# thumper_v0001.net
KiCad netlist of a schematic drawn in EAGLE
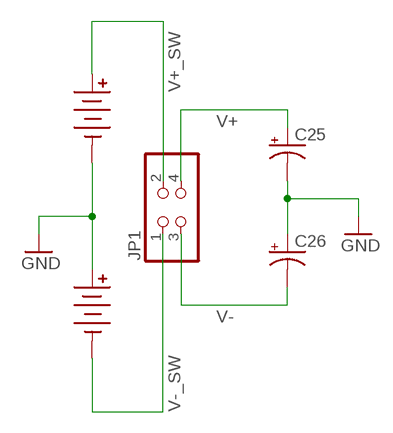
[diagram p0: schematic, sheet 1]
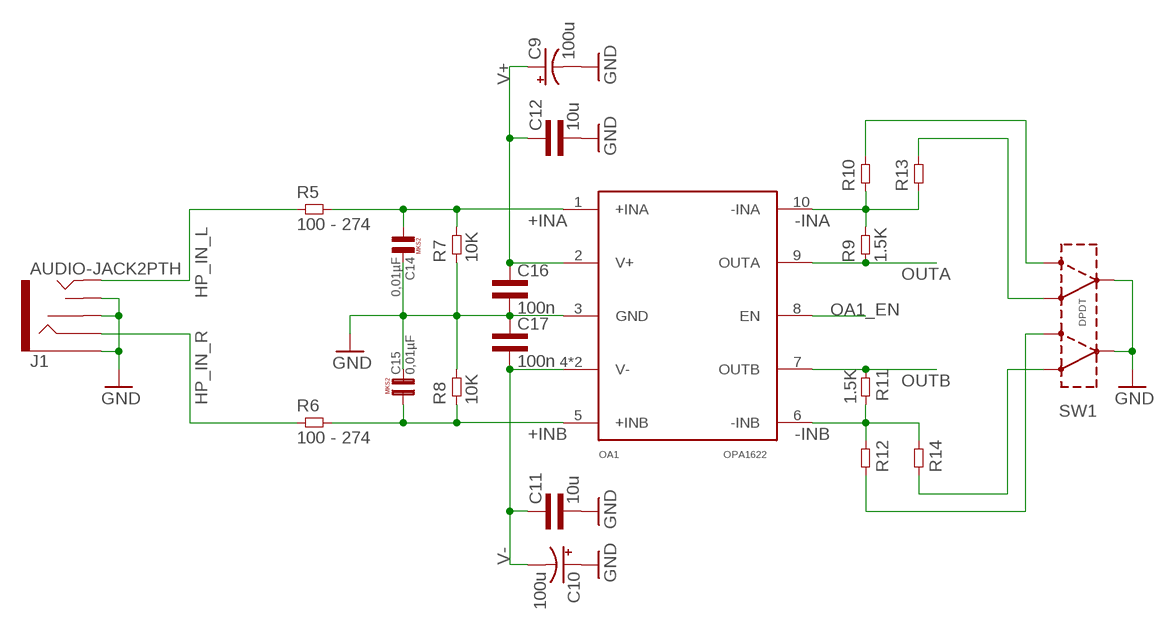
[diagram p1: schematic, sheet 2]
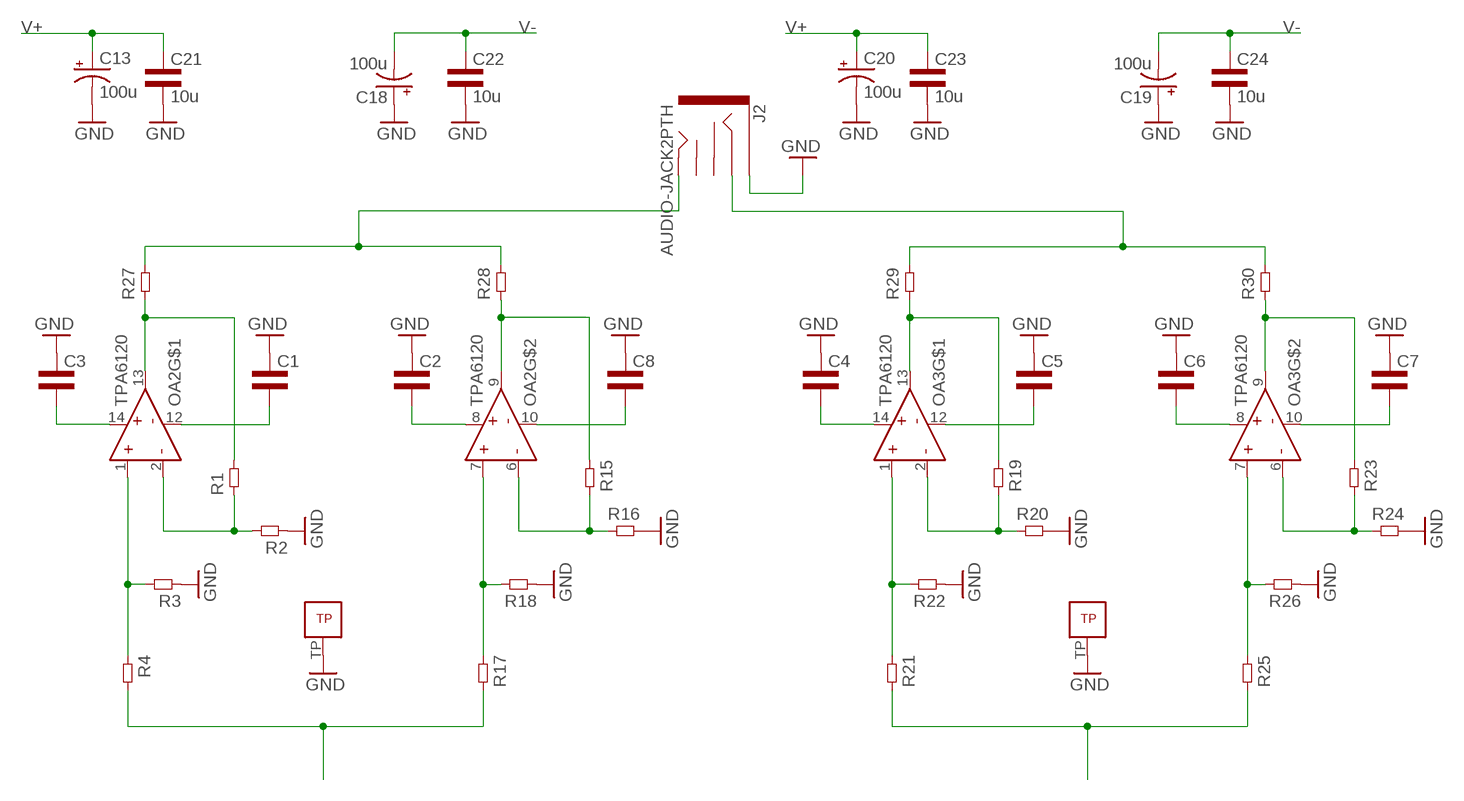
[diagram p2: schematic, sheet 3]

(export (version "E")
  (design (tool "Eeschema 10.0.6"))
  (components
    (comp (ref "C1")
      (value "CAP0603L3")
      (footprint "eagle-import:0603L3")
      (libsource (lib "eagle-import") (part "CAP0603L3"))
    )
    (comp (ref "C2")
      (value "CAP0603L3")
      (footprint "eagle-import:0603L3")
      (libsource (lib "eagle-import") (part "CAP0603L3"))
    )
    (comp (ref "C3")
      (value "CAP0603L3")
      (footprint "eagle-import:0603L3")
      (libsource (lib "eagle-import") (part "CAP0603L3"))
    )
    (comp (ref "C4")
      (value "CAP0603L3")
      (footprint "eagle-import:0603L3")
      (libsource (lib "eagle-import") (part "CAP0603L3"))
    )
    (comp (ref "C5")
      (value "CAP0603L3")
      (footprint "eagle-import:0603L3")
      (libsource (lib "eagle-import") (part "CAP0603L3"))
    )
    (comp (ref "C6")
      (value "CAP0603L3")
      (footprint "eagle-import:0603L3")
      (libsource (lib "eagle-import") (part "CAP0603L3"))
    )
    (comp (ref "C7")
      (value "CAP0603L3")
      (footprint "eagle-import:0603L3")
      (libsource (lib "eagle-import") (part "CAP0603L3"))
    )
    (comp (ref "C8")
      (value "CAP0603L3")
      (footprint "eagle-import:0603L3")
      (libsource (lib "eagle-import") (part "CAP0603L3"))
    )
    (comp (ref "C13")
      (value "100u")
      (footprint "eagle-import:CT7343")
      (libsource (lib "eagle-import") (part "CPOL-USCT7343"))
    )
    (comp (ref "C18")
      (value "100u")
      (footprint "eagle-import:CT7343")
      (libsource (lib "eagle-import") (part "CPOL-USCT7343"))
    )
    (comp (ref "C19")
      (value "100u")
      (footprint "eagle-import:CT7343")
      (libsource (lib "eagle-import") (part "CPOL-USCT7343"))
    )
    (comp (ref "C20")
      (value "100u")
      (footprint "eagle-import:CT7343")
      (libsource (lib "eagle-import") (part "CPOL-USCT7343"))
    )
    (comp (ref "C21")
      (value "10u")
      (footprint "eagle-import:0805L3")
      (libsource (lib "eagle-import") (part "CAP0805L3"))
    )
    (comp (ref "C22")
      (value "10u")
      (footprint "eagle-import:0805L3")
      (libsource (lib "eagle-import") (part "CAP0805L3"))
    )
    (comp (ref "C23")
      (value "10u")
      (footprint "eagle-import:0805L3")
      (libsource (lib "eagle-import") (part "CAP0805L3"))
    )
    (comp (ref "C24")
      (value "10u")
      (footprint "eagle-import:0805L3")
      (libsource (lib "eagle-import") (part "CAP0805L3"))
    )
    (comp (ref "J2")
      (value "AUDIO-JACK2PTH")
      (footprint "eagle-import:AUDIO-JACK")
      (libsource (lib "eagle-import") (part "AUDIO-JACK2PTH"))
    )
    (comp (ref "OA2")
      (value "TPA6120QFN")
      (footprint "eagle-import:S-PVQFN-N14")
      (libsource (lib "eagle-import") (part "TPA6120QFN"))
    )
    (comp (ref "OA3")
      (value "TPA6120QFN")
      (footprint "eagle-import:S-PVQFN-N14")
      (libsource (lib "eagle-import") (part "TPA6120QFN"))
    )
    (comp (ref "R1")
      (value "RES0603L3")
      (footprint "eagle-import:0603L3")
      (libsource (lib "eagle-import") (part "RES0603L3"))
    )
    (comp (ref "R2")
      (value "RES0603L3")
      (footprint "eagle-import:0603L3")
      (libsource (lib "eagle-import") (part "RES0603L3"))
    )
    (comp (ref "R3")
      (value "RES0603L3")
      (footprint "eagle-import:0603L3")
      (libsource (lib "eagle-import") (part "RES0603L3"))
    )
    (comp (ref "R4")
      (value "RES0603L3")
      (footprint "eagle-import:0603L3")
      (libsource (lib "eagle-import") (part "RES0603L3"))
    )
    (comp (ref "R15")
      (value "RES0603L3")
      (footprint "eagle-import:0603L3")
      (libsource (lib "eagle-import") (part "RES0603L3"))
    )
    (comp (ref "R16")
      (value "RES0603L3")
      (footprint "eagle-import:0603L3")
      (libsource (lib "eagle-import") (part "RES0603L3"))
    )
    (comp (ref "R17")
      (value "RES0603L3")
      (footprint "eagle-import:0603L3")
      (libsource (lib "eagle-import") (part "RES0603L3"))
    )
    (comp (ref "R18")
      (value "RES0603L3")
      (footprint "eagle-import:0603L3")
      (libsource (lib "eagle-import") (part "RES0603L3"))
    )
    (comp (ref "R19")
      (value "RES0603L3")
      (footprint "eagle-import:0603L3")
      (libsource (lib "eagle-import") (part "RES0603L3"))
    )
    (comp (ref "R20")
      (value "RES0603L3")
      (footprint "eagle-import:0603L3")
      (libsource (lib "eagle-import") (part "RES0603L3"))
    )
    (comp (ref "R21")
      (value "RES0603L3")
      (footprint "eagle-import:0603L3")
      (libsource (lib "eagle-import") (part "RES0603L3"))
    )
    (comp (ref "R22")
      (value "RES0603L3")
      (footprint "eagle-import:0603L3")
      (libsource (lib "eagle-import") (part "RES0603L3"))
    )
    (comp (ref "R23")
      (value "RES0603L3")
      (footprint "eagle-import:0603L3")
      (libsource (lib "eagle-import") (part "RES0603L3"))
    )
    (comp (ref "R24")
      (value "RES0603L3")
      (footprint "eagle-import:0603L3")
      (libsource (lib "eagle-import") (part "RES0603L3"))
    )
    (comp (ref "R25")
      (value "RES0603L3")
      (footprint "eagle-import:0603L3")
      (libsource (lib "eagle-import") (part "RES0603L3"))
    )
    (comp (ref "R26")
      (value "RES0603L3")
      (footprint "eagle-import:0603L3")
      (libsource (lib "eagle-import") (part "RES0603L3"))
    )
    (comp (ref "R27")
      (value "RES0805L3")
      (footprint "eagle-import:0805L3")
      (libsource (lib "eagle-import") (part "RES0805L3"))
    )
    (comp (ref "R28")
      (value "RES0805L3")
      (footprint "eagle-import:0805L3")
      (libsource (lib "eagle-import") (part "RES0805L3"))
    )
    (comp (ref "R29")
      (value "RES0805L3")
      (footprint "eagle-import:0805L3")
      (libsource (lib "eagle-import") (part "RES0805L3"))
    )
    (comp (ref "R30")
      (value "RES0805L3")
      (footprint "eagle-import:0805L3")
      (libsource (lib "eagle-import") (part "RES0805L3"))
    )
    (comp (ref "BATT1")
      (value "BATT_9V")
      (footprint "eagle-import:9V_FEMALE")
      (libsource (lib "eagle-import") (part "BATT_9V"))
    )
    (comp (ref "BATT2")
      (value "BATT_9V")
      (footprint "eagle-import:9V_FEMALE")
      (libsource (lib "eagle-import") (part "BATT_9V"))
    )
    (comp (ref "C25")
      (value "CPOL-US153CLV-1010")
      (footprint "eagle-import:153CLV-1010")
      (libsource (lib "eagle-import") (part "CPOL-US153CLV-1010"))
    )
    (comp (ref "C26")
      (value "CPOL-US153CLV-1010")
      (footprint "eagle-import:153CLV-1010")
      (libsource (lib "eagle-import") (part "CPOL-US153CLV-1010"))
    )
    (comp (ref "JP1")
      (value "PINHD-2X2")
      (footprint "eagle-import:2X02")
      (libsource (lib "eagle-import") (part "PINHD-2X2"))
    )
    (comp (ref "C9")
      (value "100u")
      (footprint "eagle-import:CT7343")
      (libsource (lib "eagle-import") (part "CPOL-USCT7343"))
    )
    (comp (ref "C10")
      (value "100u")
      (footprint "eagle-import:CT7343")
      (libsource (lib "eagle-import") (part "CPOL-USCT7343"))
    )
    (comp (ref "C11")
      (value "10u")
      (footprint "eagle-import:0805L3")
      (libsource (lib "eagle-import") (part "CAP0805L3"))
    )
    (comp (ref "C12")
      (value "10u")
      (footprint "eagle-import:0805L3")
      (libsource (lib "eagle-import") (part "CAP0805L3"))
    )
    (comp (ref "C14")
      (value "0,01µF")
      (footprint "eagle-import:R5B2K5")
      (libsource (lib "eagle-import") (part "0,01µF"))
    )
    (comp (ref "C15")
      (value "0,01µF")
      (footprint "eagle-import:R5B2K5")
      (libsource (lib "eagle-import") (part "0,01µF"))
    )
    (comp (ref "C16")
      (value "100n")
      (footprint "eagle-import:0603L3")
      (libsource (lib "eagle-import") (part "CAP0603L3"))
    )
    (comp (ref "C17")
      (value "100n")
      (footprint "eagle-import:0603L3")
      (libsource (lib "eagle-import") (part "CAP0603L3"))
    )
    (comp (ref "J1")
      (value "AUDIO-JACK2PTH")
      (footprint "eagle-import:AUDIO-JACK")
      (libsource (lib "eagle-import") (part "AUDIO-JACK2PTH"))
    )
    (comp (ref "OA1")
      (value "OPA1622")
      (footprint "eagle-import:S-PVSON-N10")
      (libsource (lib "eagle-import") (part "OPA1622"))
    )
    (comp (ref "R5")
      (value "100 - 274")
      (footprint "eagle-import:0603L3")
      (libsource (lib "eagle-import") (part "RES0603L3"))
    )
    (comp (ref "R6")
      (value "100 - 274")
      (footprint "eagle-import:0603L3")
      (libsource (lib "eagle-import") (part "RES0603L3"))
    )
    (comp (ref "R7")
      (value "10K")
      (footprint "eagle-import:0603L3")
      (libsource (lib "eagle-import") (part "RES0603L3"))
    )
    (comp (ref "R8")
      (value "10K")
      (footprint "eagle-import:0603L3")
      (libsource (lib "eagle-import") (part "RES0603L3"))
    )
    (comp (ref "R9")
      (value "1.5K")
      (footprint "eagle-import:0603L3")
      (libsource (lib "eagle-import") (part "RES0603L3"))
    )
    (comp (ref "R10")
      (value "RES0603L3")
      (footprint "eagle-import:0603L3")
      (libsource (lib "eagle-import") (part "RES0603L3"))
    )
    (comp (ref "R11")
      (value "1.5K")
      (footprint "eagle-import:0603L3")
      (libsource (lib "eagle-import") (part "RES0603L3"))
    )
    (comp (ref "R12")
      (value "RES0603L3")
      (footprint "eagle-import:0603L3")
      (libsource (lib "eagle-import") (part "RES0603L3"))
    )
    (comp (ref "R13")
      (value "RES0603L3")
      (footprint "eagle-import:0603L3")
      (libsource (lib "eagle-import") (part "RES0603L3"))
    )
    (comp (ref "R14")
      (value "RES0603L3")
      (footprint "eagle-import:0603L3")
      (libsource (lib "eagle-import") (part "RES0603L3"))
    )
    (comp (ref "SW1")
      (value "DPDTDPDT-2X2.5")
      (footprint "eagle-import:DPDT-2X2.5")
      (libsource (lib "eagle-import") (part "DPDTDPDT-2X2.5"))
    )
  )
  (nets
    (net (code "1") (name "+INA") (class "Default")
      (node (ref "C14") (pin "1") (pinfunction "1_1") (pintype "passive"))
      (node (ref "OA1") (pin "1") (pinfunction "+INA_1") (pintype "bidirectional"))
      (node (ref "R5") (pin "P$2") (pinfunction "2_P$2") (pintype "bidirectional"))
      (node (ref "R7") (pin "P$2") (pinfunction "2_P$2") (pintype "bidirectional"))
    )
    (net (code "2") (name "+INB") (class "Default")
      (node (ref "C15") (pin "1") (pinfunction "1_1") (pintype "passive"))
      (node (ref "OA1") (pin "5") (pinfunction "+INB_5") (pintype "bidirectional"))
      (node (ref "R6") (pin "P$2") (pinfunction "2_P$2") (pintype "bidirectional"))
      (node (ref "R8") (pin "P$1") (pinfunction "1_P$1") (pintype "bidirectional"))
    )
    (net (code "3") (name "-INA") (class "Default")
      (node (ref "OA1") (pin "10") (pinfunction "-INA_10") (pintype "bidirectional"))
      (node (ref "R10") (pin "P$1") (pinfunction "1_P$1") (pintype "bidirectional"))
      (node (ref "R13") (pin "P$1") (pinfunction "1_P$1") (pintype "bidirectional"))
      (node (ref "R9") (pin "P$2") (pinfunction "2_P$2") (pintype "bidirectional"))
    )
    (net (code "4") (name "-INB") (class "Default")
      (node (ref "OA1") (pin "6") (pinfunction "-INB_6") (pintype "bidirectional"))
      (node (ref "R11") (pin "P$2") (pinfunction "2_P$2") (pintype "bidirectional"))
      (node (ref "R12") (pin "P$1") (pinfunction "1_P$1") (pintype "bidirectional"))
      (node (ref "R14") (pin "P$1") (pinfunction "1_P$1") (pintype "bidirectional"))
    )
    (net (code "5") (name "GND") (class "Default")
      (node (ref "BATT1") (pin "N1") (pinfunction "NEG_N1") (pintype "bidirectional"))
      (node (ref "BATT1") (pin "N2") (pinfunction "NEG_N2") (pintype "bidirectional"))
      (node (ref "BATT1") (pin "N3") (pinfunction "NEG_N3") (pintype "bidirectional"))
      (node (ref "BATT2") (pin "P1") (pinfunction "POS_P1") (pintype "bidirectional"))
      (node (ref "BATT2") (pin "P2") (pinfunction "POS_P2") (pintype "bidirectional"))
      (node (ref "BATT2") (pin "P3") (pinfunction "POS_P3") (pintype "bidirectional"))
      (node (ref "C1") (pin "P$1") (pinfunction "1_P$1") (pintype "bidirectional"))
      (node (ref "C10") (pin "+") (pinfunction "+_+") (pintype "passive"))
      (node (ref "C11") (pin "2") (pinfunction "2_2") (pintype "bidirectional"))
      (node (ref "C12") (pin "2") (pinfunction "2_2") (pintype "bidirectional"))
      (node (ref "C13") (pin "-") (pinfunction "-_-") (pintype "passive"))
      (node (ref "C14") (pin "2") (pinfunction "2_2") (pintype "passive"))
      (node (ref "C15") (pin "2") (pinfunction "2_2") (pintype "passive"))
      (node (ref "C16") (pin "P$2") (pinfunction "2_P$2") (pintype "bidirectional"))
      (node (ref "C17") (pin "P$1") (pinfunction "1_P$1") (pintype "bidirectional"))
      (node (ref "C18") (pin "+") (pinfunction "+_+") (pintype "passive"))
      (node (ref "C19") (pin "+") (pinfunction "+_+") (pintype "passive"))
      (node (ref "C2") (pin "P$1") (pinfunction "1_P$1") (pintype "bidirectional"))
      (node (ref "C20") (pin "-") (pinfunction "-_-") (pintype "passive"))
      (node (ref "C21") (pin "2") (pinfunction "2_2") (pintype "bidirectional"))
      (node (ref "C22") (pin "2") (pinfunction "2_2") (pintype "bidirectional"))
      (node (ref "C23") (pin "2") (pinfunction "2_2") (pintype "bidirectional"))
      (node (ref "C24") (pin "2") (pinfunction "2_2") (pintype "bidirectional"))
      (node (ref "C25") (pin "-") (pinfunction "-_-") (pintype "passive"))
      (node (ref "C26") (pin "+") (pinfunction "+_+") (pintype "passive"))
      (node (ref "C3") (pin "P$1") (pinfunction "1_P$1") (pintype "bidirectional"))
      (node (ref "C4") (pin "P$1") (pinfunction "1_P$1") (pintype "bidirectional"))
      (node (ref "C5") (pin "P$1") (pinfunction "1_P$1") (pintype "bidirectional"))
      (node (ref "C6") (pin "P$1") (pinfunction "1_P$1") (pintype "bidirectional"))
      (node (ref "C7") (pin "P$1") (pinfunction "1_P$1") (pintype "bidirectional"))
      (node (ref "C8") (pin "P$1") (pinfunction "1_P$1") (pintype "bidirectional"))
      (node (ref "C9") (pin "-") (pinfunction "-_-") (pintype "passive"))
      (node (ref "J1") (pin "RSH") (pinfunction "RSH_RSH") (pintype "bidirectional"))
      (node (ref "J1") (pin "SLEEVE") (pinfunction "SLEEVE_SLEEVE") (pintype "bidirectional"))
      (node (ref "J1") (pin "TSH") (pinfunction "TSH_TSH") (pintype "bidirectional"))
      (node (ref "J2") (pin "SLEEVE") (pinfunction "SLEEVE_SLEEVE") (pintype "bidirectional"))
      (node (ref "OA1") (pin "3") (pinfunction "GND_3") (pintype "bidirectional"))
      (node (ref "OA2") (pin "TP") (pinfunction "TP_TP") (pintype "bidirectional"))
      (node (ref "OA3") (pin "TP") (pinfunction "TP_TP") (pintype "bidirectional"))
      (node (ref "R16") (pin "P$2") (pinfunction "2_P$2") (pintype "bidirectional"))
      (node (ref "R18") (pin "P$1") (pinfunction "1_P$1") (pintype "bidirectional"))
      (node (ref "R2") (pin "P$1") (pinfunction "1_P$1") (pintype "bidirectional"))
      (node (ref "R20") (pin "P$2") (pinfunction "2_P$2") (pintype "bidirectional"))
      (node (ref "R22") (pin "P$1") (pinfunction "1_P$1") (pintype "bidirectional"))
      (node (ref "R24") (pin "P$2") (pinfunction "2_P$2") (pintype "bidirectional"))
      (node (ref "R26") (pin "P$1") (pinfunction "1_P$1") (pintype "bidirectional"))
      (node (ref "R3") (pin "P$1") (pinfunction "1_P$1") (pintype "bidirectional"))
      (node (ref "R7") (pin "P$1") (pinfunction "1_P$1") (pintype "bidirectional"))
      (node (ref "R8") (pin "P$2") (pinfunction "2_P$2") (pintype "bidirectional"))
      (node (ref "SW1") (pin "2") (pinfunction "INA_2") (pintype "bidirectional"))
      (node (ref "SW1") (pin "5") (pinfunction "INB_5") (pintype "bidirectional"))
    )
    (net (code "6") (name "HP_IN_L") (class "Default")
      (node (ref "J1") (pin "TIP") (pinfunction "TIP_TIP") (pintype "bidirectional"))
      (node (ref "R5") (pin "P$1") (pinfunction "1_P$1") (pintype "bidirectional"))
    )
    (net (code "7") (name "HP_IN_R") (class "Default")
      (node (ref "J1") (pin "RING") (pinfunction "RING_RING") (pintype "bidirectional"))
      (node (ref "R6") (pin "P$1") (pinfunction "1_P$1") (pintype "bidirectional"))
    )
    (net (code "8") (name "Net-(J2-PadRING)") (class "Default")
      (node (ref "J2") (pin "RING") (pinfunction "RING_RING") (pintype "bidirectional"))
      (node (ref "R29") (pin "2") (pinfunction "2_2") (pintype "bidirectional"))
      (node (ref "R30") (pin "2") (pinfunction "2_2") (pintype "bidirectional"))
    )
    (net (code "9") (name "Net-(J2-PadTIP)") (class "Default")
      (node (ref "J2") (pin "TIP") (pinfunction "TIP_TIP") (pintype "bidirectional"))
      (node (ref "R27") (pin "2") (pinfunction "2_2") (pintype "bidirectional"))
      (node (ref "R28") (pin "2") (pinfunction "2_2") (pintype "bidirectional"))
    )
    (net (code "10") (name "Net-(OA2A-IN+)") (class "Default")
      (node (ref "OA2") (pin "1") (pinfunction "IN+_1") (pintype "bidirectional"))
      (node (ref "R3") (pin "P$2") (pinfunction "2_P$2") (pintype "bidirectional"))
      (node (ref "R4") (pin "P$1") (pinfunction "1_P$1") (pintype "bidirectional"))
    )
    (net (code "11") (name "Net-(OA2A-IN-)") (class "Default")
      (node (ref "OA2") (pin "2") (pinfunction "IN-_2") (pintype "bidirectional"))
      (node (ref "R1") (pin "P$1") (pinfunction "1_P$1") (pintype "bidirectional"))
      (node (ref "R2") (pin "P$2") (pinfunction "2_P$2") (pintype "bidirectional"))
    )
    (net (code "12") (name "Net-(OA2A-OUT)") (class "Default")
      (node (ref "OA2") (pin "13") (pinfunction "OUT_13") (pintype "bidirectional"))
      (node (ref "R1") (pin "P$2") (pinfunction "2_P$2") (pintype "bidirectional"))
      (node (ref "R27") (pin "1") (pinfunction "1_1") (pintype "bidirectional"))
    )
    (net (code "13") (name "Net-(OA2B-IN+)") (class "Default")
      (node (ref "OA2") (pin "7") (pinfunction "IN+_7") (pintype "bidirectional"))
      (node (ref "R17") (pin "P$1") (pinfunction "1_P$1") (pintype "bidirectional"))
      (node (ref "R18") (pin "P$2") (pinfunction "2_P$2") (pintype "bidirectional"))
    )
    (net (code "14") (name "Net-(OA2B-IN-)") (class "Default")
      (node (ref "OA2") (pin "6") (pinfunction "IN-_6") (pintype "bidirectional"))
      (node (ref "R15") (pin "P$2") (pinfunction "2_P$2") (pintype "bidirectional"))
      (node (ref "R16") (pin "P$1") (pinfunction "1_P$1") (pintype "bidirectional"))
    )
    (net (code "15") (name "Net-(OA2B-OUT)") (class "Default")
      (node (ref "OA2") (pin "9") (pinfunction "OUT_9") (pintype "bidirectional"))
      (node (ref "R15") (pin "P$1") (pinfunction "1_P$1") (pintype "bidirectional"))
      (node (ref "R28") (pin "1") (pinfunction "1_1") (pintype "bidirectional"))
    )
    (net (code "16") (name "Net-(OA3A-IN+)") (class "Default")
      (node (ref "OA3") (pin "1") (pinfunction "IN+_1") (pintype "bidirectional"))
      (node (ref "R21") (pin "P$1") (pinfunction "1_P$1") (pintype "bidirectional"))
      (node (ref "R22") (pin "P$2") (pinfunction "2_P$2") (pintype "bidirectional"))
    )
    (net (code "17") (name "Net-(OA3A-IN-)") (class "Default")
      (node (ref "OA3") (pin "2") (pinfunction "IN-_2") (pintype "bidirectional"))
      (node (ref "R19") (pin "P$2") (pinfunction "2_P$2") (pintype "bidirectional"))
      (node (ref "R20") (pin "P$1") (pinfunction "1_P$1") (pintype "bidirectional"))
    )
    (net (code "18") (name "Net-(OA3A-OUT)") (class "Default")
      (node (ref "OA3") (pin "13") (pinfunction "OUT_13") (pintype "bidirectional"))
      (node (ref "R19") (pin "P$1") (pinfunction "1_P$1") (pintype "bidirectional"))
      (node (ref "R29") (pin "1") (pinfunction "1_1") (pintype "bidirectional"))
    )
    (net (code "19") (name "Net-(OA3B-IN+)") (class "Default")
      (node (ref "OA3") (pin "7") (pinfunction "IN+_7") (pintype "bidirectional"))
      (node (ref "R25") (pin "P$1") (pinfunction "1_P$1") (pintype "bidirectional"))
      (node (ref "R26") (pin "P$2") (pinfunction "2_P$2") (pintype "bidirectional"))
    )
    (net (code "20") (name "Net-(OA3B-IN-)") (class "Default")
      (node (ref "OA3") (pin "6") (pinfunction "IN-_6") (pintype "bidirectional"))
      (node (ref "R23") (pin "P$2") (pinfunction "2_P$2") (pintype "bidirectional"))
      (node (ref "R24") (pin "P$1") (pinfunction "1_P$1") (pintype "bidirectional"))
    )
    (net (code "21") (name "Net-(OA3B-OUT)") (class "Default")
      (node (ref "OA3") (pin "9") (pinfunction "OUT_9") (pintype "bidirectional"))
      (node (ref "R23") (pin "P$1") (pinfunction "1_P$1") (pintype "bidirectional"))
      (node (ref "R30") (pin "1") (pinfunction "1_1") (pintype "bidirectional"))
    )
    (net (code "22") (name "Net-(R10-2)") (class "Default")
      (node (ref "R10") (pin "P$2") (pinfunction "2_P$2") (pintype "bidirectional"))
      (node (ref "SW1") (pin "6") (pinfunction "OUTB2_6") (pintype "bidirectional"))
    )
    (net (code "23") (name "Net-(R12-2)") (class "Default")
      (node (ref "R12") (pin "P$2") (pinfunction "2_P$2") (pintype "bidirectional"))
      (node (ref "SW1") (pin "3") (pinfunction "OUTA2_3") (pintype "bidirectional"))
    )
    (net (code "24") (name "Net-(R13-2)") (class "Default")
      (node (ref "R13") (pin "P$2") (pinfunction "2_P$2") (pintype "bidirectional"))
      (node (ref "SW1") (pin "4") (pinfunction "OUTB1_4") (pintype "bidirectional"))
    )
    (net (code "25") (name "Net-(R14-2)") (class "Default")
      (node (ref "R14") (pin "P$2") (pinfunction "2_P$2") (pintype "bidirectional"))
      (node (ref "SW1") (pin "1") (pinfunction "OUTA1_1") (pintype "bidirectional"))
    )
    (net (code "26") (name "OA1_EN") (class "Default")
      (node (ref "OA1") (pin "8") (pinfunction "EN_8") (pintype "bidirectional"))
    )
    (net (code "27") (name "OUTA") (class "Default")
      (node (ref "OA1") (pin "9") (pinfunction "OUTA_9") (pintype "bidirectional"))
      (node (ref "R17") (pin "P$2") (pinfunction "2_P$2") (pintype "bidirectional"))
      (node (ref "R4") (pin "P$2") (pinfunction "2_P$2") (pintype "bidirectional"))
      (node (ref "R9") (pin "P$1") (pinfunction "1_P$1") (pintype "bidirectional"))
    )
    (net (code "28") (name "OUTB") (class "Default")
      (node (ref "OA1") (pin "7") (pinfunction "OUTB_7") (pintype "bidirectional"))
      (node (ref "R11") (pin "P$1") (pinfunction "1_P$1") (pintype "bidirectional"))
      (node (ref "R21") (pin "P$2") (pinfunction "2_P$2") (pintype "bidirectional"))
      (node (ref "R25") (pin "P$2") (pinfunction "2_P$2") (pintype "bidirectional"))
    )
    (net (code "29") (name "V+") (class "Default")
      (node (ref "C12") (pin "1") (pinfunction "1_1") (pintype "bidirectional"))
      (node (ref "C13") (pin "+") (pinfunction "+_+") (pintype "passive"))
      (node (ref "C16") (pin "P$1") (pinfunction "1_P$1") (pintype "bidirectional"))
      (node (ref "C2") (pin "P$2") (pinfunction "2_P$2") (pintype "bidirectional"))
      (node (ref "C20") (pin "+") (pinfunction "+_+") (pintype "passive"))
      (node (ref "C21") (pin "1") (pinfunction "1_1") (pintype "bidirectional"))
      (node (ref "C23") (pin "1") (pinfunction "1_1") (pintype "bidirectional"))
      (node (ref "C25") (pin "+") (pinfunction "+_+") (pintype "passive"))
      (node (ref "C3") (pin "P$2") (pinfunction "2_P$2") (pintype "bidirectional"))
      (node (ref "C4") (pin "P$2") (pinfunction "2_P$2") (pintype "bidirectional"))
      (node (ref "C6") (pin "P$2") (pinfunction "2_P$2") (pintype "bidirectional"))
      (node (ref "C9") (pin "+") (pinfunction "+_+") (pintype "passive"))
      (node (ref "JP1") (pin "4") (pinfunction "4_4") (pintype "passive"))
      (node (ref "OA1") (pin "2") (pinfunction "V+_2") (pintype "bidirectional"))
      (node (ref "OA2") (pin "14") (pinfunction "V+_14") (pintype "bidirectional"))
      (node (ref "OA2") (pin "8") (pinfunction "V+_8") (pintype "bidirectional"))
      (node (ref "OA3") (pin "14") (pinfunction "V+_14") (pintype "bidirectional"))
      (node (ref "OA3") (pin "8") (pinfunction "V+_8") (pintype "bidirectional"))
    )
    (net (code "30") (name "V+_SW") (class "Default")
      (node (ref "BATT1") (pin "P1") (pinfunction "POS_P1") (pintype "bidirectional"))
      (node (ref "BATT1") (pin "P2") (pinfunction "POS_P2") (pintype "bidirectional"))
      (node (ref "BATT1") (pin "P3") (pinfunction "POS_P3") (pintype "bidirectional"))
      (node (ref "JP1") (pin "2") (pinfunction "2_2") (pintype "passive"))
    )
    (net (code "31") (name "V-") (class "Default")
      (node (ref "C1") (pin "P$2") (pinfunction "2_P$2") (pintype "bidirectional"))
      (node (ref "C10") (pin "-") (pinfunction "-_-") (pintype "passive"))
      (node (ref "C11") (pin "1") (pinfunction "1_1") (pintype "bidirectional"))
      (node (ref "C17") (pin "P$2") (pinfunction "2_P$2") (pintype "bidirectional"))
      (node (ref "C18") (pin "-") (pinfunction "-_-") (pintype "passive"))
      (node (ref "C19") (pin "-") (pinfunction "-_-") (pintype "passive"))
      (node (ref "C22") (pin "1") (pinfunction "1_1") (pintype "bidirectional"))
      (node (ref "C24") (pin "1") (pinfunction "1_1") (pintype "bidirectional"))
      (node (ref "C26") (pin "-") (pinfunction "-_-") (pintype "passive"))
      (node (ref "C5") (pin "P$2") (pinfunction "2_P$2") (pintype "bidirectional"))
      (node (ref "C7") (pin "P$2") (pinfunction "2_P$2") (pintype "bidirectional"))
      (node (ref "C8") (pin "P$2") (pinfunction "2_P$2") (pintype "bidirectional"))
      (node (ref "JP1") (pin "3") (pinfunction "3_3") (pintype "passive"))
      (node (ref "OA1") (pin "4") (pinfunction "V-_4") (pintype "bidirectional"))
      (node (ref "OA1") (pin "TP") (pinfunction "V-_TP") (pintype "bidirectional"))
      (node (ref "OA2") (pin "10") (pinfunction "V-_10") (pintype "bidirectional"))
      (node (ref "OA2") (pin "12") (pinfunction "V-_12") (pintype "bidirectional"))
      (node (ref "OA3") (pin "10") (pinfunction "V-_10") (pintype "bidirectional"))
      (node (ref "OA3") (pin "12") (pinfunction "V-_12") (pintype "bidirectional"))
    )
    (net (code "32") (name "V-_SW") (class "Default")
      (node (ref "BATT2") (pin "N1") (pinfunction "NEG_N1") (pintype "bidirectional"))
      (node (ref "BATT2") (pin "N2") (pinfunction "NEG_N2") (pintype "bidirectional"))
      (node (ref "BATT2") (pin "N3") (pinfunction "NEG_N3") (pintype "bidirectional"))
      (node (ref "JP1") (pin "1") (pinfunction "1_1") (pintype "passive"))
    )
    (net (code "33") (name "unconnected-(J2-PadRSH)") (class "Default")
      (node (ref "J2") (pin "RSH") (pinfunction "RSH_RSH") (pintype "bidirectional"))
    )
    (net (code "34") (name "unconnected-(J2-PadTSH)") (class "Default")
      (node (ref "J2") (pin "TSH") (pinfunction "TSH_TSH") (pintype "bidirectional"))
    )
  )
)
